# alt1.net
KiCad netlist of a schematic drawn in EAGLE
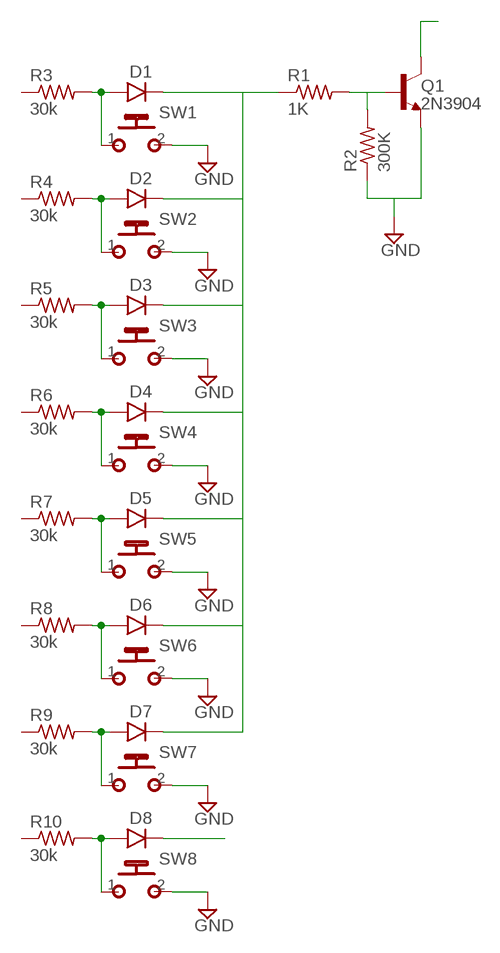
[diagram p0: schematic, sheet 1]

(export (version "E")
  (design (tool "Eeschema 10.0.6"))
  (components
    (comp (ref "D1")
      (value "1N4148-3")
      (footprint "eagle-import:DO35-3")
      (libsource (lib "eagle-import") (part "1N4148-3"))
    )
    (comp (ref "D2")
      (value "1N4148-3")
      (footprint "eagle-import:DO35-3")
      (libsource (lib "eagle-import") (part "1N4148-3"))
    )
    (comp (ref "D3")
      (value "1N4148-3")
      (footprint "eagle-import:DO35-3")
      (libsource (lib "eagle-import") (part "1N4148-3"))
    )
    (comp (ref "D4")
      (value "1N4148-3")
      (footprint "eagle-import:DO35-3")
      (libsource (lib "eagle-import") (part "1N4148-3"))
    )
    (comp (ref "D5")
      (value "1N4148-3")
      (footprint "eagle-import:DO35-3")
      (libsource (lib "eagle-import") (part "1N4148-3"))
    )
    (comp (ref "D6")
      (value "1N4148-3")
      (footprint "eagle-import:DO35-3")
      (libsource (lib "eagle-import") (part "1N4148-3"))
    )
    (comp (ref "D7")
      (value "1N4148-3")
      (footprint "eagle-import:DO35-3")
      (libsource (lib "eagle-import") (part "1N4148-3"))
    )
    (comp (ref "D8")
      (value "1N4148-3")
      (footprint "eagle-import:DO35-3")
      (libsource (lib "eagle-import") (part "1N4148-3"))
    )
    (comp (ref "Q1")
      (value "2N3904")
      (footprint "eagle-import:TO92-")
      (libsource (lib "eagle-import") (part "2N3904"))
    )
    (comp (ref "R1")
      (value "1K")
      (footprint "eagle-import:R0207_3")
      (libsource (lib "eagle-import") (part "6MM.3"))
    )
    (comp (ref "R2")
      (value "300K")
      (footprint "eagle-import:R0207_3")
      (libsource (lib "eagle-import") (part "6MM.3"))
    )
    (comp (ref "R3")
      (value "30k")
      (footprint "eagle-import:R0207_3")
      (libsource (lib "eagle-import") (part "6MM.3"))
    )
    (comp (ref "R4")
      (value "30k")
      (footprint "eagle-import:R0207_3")
      (libsource (lib "eagle-import") (part "6MM.3"))
    )
    (comp (ref "R5")
      (value "30k")
      (footprint "eagle-import:R0207_3")
      (libsource (lib "eagle-import") (part "6MM.3"))
    )
    (comp (ref "R6")
      (value "30k")
      (footprint "eagle-import:R0207_3")
      (libsource (lib "eagle-import") (part "6MM.3"))
    )
    (comp (ref "R7")
      (value "30k")
      (footprint "eagle-import:R0207_3")
      (libsource (lib "eagle-import") (part "6MM.3"))
    )
    (comp (ref "R8")
      (value "30k")
      (footprint "eagle-import:R0207_3")
      (libsource (lib "eagle-import") (part "6MM.3"))
    )
    (comp (ref "R9")
      (value "30k")
      (footprint "eagle-import:R0207_3")
      (libsource (lib "eagle-import") (part "6MM.3"))
    )
    (comp (ref "R10")
      (value "30k")
      (footprint "eagle-import:R0207_3")
      (libsource (lib "eagle-import") (part "6MM.3"))
    )
    (comp (ref "SW1")
      (value "MOMENTARYSPST1")
      (footprint "eagle-import:SPST")
      (libsource (lib "eagle-import") (part "MOMENTARYSPST1"))
    )
    (comp (ref "SW2")
      (value "MOMENTARYSPST1")
      (footprint "eagle-import:SPST")
      (libsource (lib "eagle-import") (part "MOMENTARYSPST1"))
    )
    (comp (ref "SW3")
      (value "MOMENTARYSPST1")
      (footprint "eagle-import:SPST")
      (libsource (lib "eagle-import") (part "MOMENTARYSPST1"))
    )
    (comp (ref "SW4")
      (value "MOMENTARYSPST1")
      (footprint "eagle-import:SPST")
      (libsource (lib "eagle-import") (part "MOMENTARYSPST1"))
    )
    (comp (ref "SW5")
      (value "MOMENTARYSPST1")
      (footprint "eagle-import:SPST")
      (libsource (lib "eagle-import") (part "MOMENTARYSPST1"))
    )
    (comp (ref "SW6")
      (value "MOMENTARYSPST1")
      (footprint "eagle-import:SPST")
      (libsource (lib "eagle-import") (part "MOMENTARYSPST1"))
    )
    (comp (ref "SW7")
      (value "MOMENTARYSPST1")
      (footprint "eagle-import:SPST")
      (libsource (lib "eagle-import") (part "MOMENTARYSPST1"))
    )
    (comp (ref "SW8")
      (value "MOMENTARYSPST1")
      (footprint "eagle-import:SPST")
      (libsource (lib "eagle-import") (part "MOMENTARYSPST1"))
    )
  )
  (nets
    (net (code "1") (name "GND") (class "Default")
      (node (ref "Q1") (pin "3") (pinfunction "E_3") (pintype "passive"))
      (node (ref "R2") (pin "1") (pinfunction "1_1") (pintype "passive"))
      (node (ref "SW1") (pin "2") (pinfunction "S_2") (pintype "passive"))
      (node (ref "SW2") (pin "2") (pinfunction "S_2") (pintype "passive"))
      (node (ref "SW3") (pin "2") (pinfunction "S_2") (pintype "passive"))
      (node (ref "SW4") (pin "2") (pinfunction "S_2") (pintype "passive"))
      (node (ref "SW5") (pin "2") (pinfunction "S_2") (pintype "passive"))
      (node (ref "SW6") (pin "2") (pinfunction "S_2") (pintype "passive"))
      (node (ref "SW7") (pin "2") (pinfunction "S_2") (pintype "passive"))
      (node (ref "SW8") (pin "2") (pinfunction "S_2") (pintype "passive"))
    )
    (net (code "2") (name "Net-(D1-PadC)") (class "Default")
      (node (ref "D1") (pin "C") (pinfunction "C_C") (pintype "passive"))
      (node (ref "D2") (pin "C") (pinfunction "C_C") (pintype "passive"))
      (node (ref "D3") (pin "C") (pinfunction "C_C") (pintype "passive"))
      (node (ref "D4") (pin "C") (pinfunction "C_C") (pintype "passive"))
      (node (ref "D5") (pin "C") (pinfunction "C_C") (pintype "passive"))
      (node (ref "D6") (pin "C") (pinfunction "C_C") (pintype "passive"))
      (node (ref "D7") (pin "C") (pinfunction "C_C") (pintype "passive"))
      (node (ref "R1") (pin "1") (pinfunction "1_1") (pintype "passive"))
    )
    (net (code "3") (name "Net-(Q1-B)") (class "Default")
      (node (ref "Q1") (pin "2") (pinfunction "B_2") (pintype "passive"))
      (node (ref "R1") (pin "2") (pinfunction "2_2") (pintype "passive"))
      (node (ref "R2") (pin "2") (pinfunction "2_2") (pintype "passive"))
    )
    (net (code "4") (name "Net-(SW1-P)") (class "Default")
      (node (ref "D1") (pin "A") (pinfunction "A_A") (pintype "passive"))
      (node (ref "R3") (pin "2") (pinfunction "2_2") (pintype "passive"))
      (node (ref "SW1") (pin "1") (pinfunction "P_1") (pintype "passive"))
    )
    (net (code "5") (name "Net-(SW2-P)") (class "Default")
      (node (ref "D2") (pin "A") (pinfunction "A_A") (pintype "passive"))
      (node (ref "R4") (pin "2") (pinfunction "2_2") (pintype "passive"))
      (node (ref "SW2") (pin "1") (pinfunction "P_1") (pintype "passive"))
    )
    (net (code "6") (name "Net-(SW3-P)") (class "Default")
      (node (ref "D3") (pin "A") (pinfunction "A_A") (pintype "passive"))
      (node (ref "R5") (pin "2") (pinfunction "2_2") (pintype "passive"))
      (node (ref "SW3") (pin "1") (pinfunction "P_1") (pintype "passive"))
    )
    (net (code "7") (name "Net-(SW4-P)") (class "Default")
      (node (ref "D4") (pin "A") (pinfunction "A_A") (pintype "passive"))
      (node (ref "R6") (pin "2") (pinfunction "2_2") (pintype "passive"))
      (node (ref "SW4") (pin "1") (pinfunction "P_1") (pintype "passive"))
    )
    (net (code "8") (name "Net-(SW5-P)") (class "Default")
      (node (ref "D5") (pin "A") (pinfunction "A_A") (pintype "passive"))
      (node (ref "R7") (pin "2") (pinfunction "2_2") (pintype "passive"))
      (node (ref "SW5") (pin "1") (pinfunction "P_1") (pintype "passive"))
    )
    (net (code "9") (name "Net-(SW6-P)") (class "Default")
      (node (ref "D6") (pin "A") (pinfunction "A_A") (pintype "passive"))
      (node (ref "R8") (pin "2") (pinfunction "2_2") (pintype "passive"))
      (node (ref "SW6") (pin "1") (pinfunction "P_1") (pintype "passive"))
    )
    (net (code "10") (name "Net-(SW7-P)") (class "Default")
      (node (ref "D7") (pin "A") (pinfunction "A_A") (pintype "passive"))
      (node (ref "R9") (pin "2") (pinfunction "2_2") (pintype "passive"))
      (node (ref "SW7") (pin "1") (pinfunction "P_1") (pintype "passive"))
    )
    (net (code "11") (name "Net-(SW8-P)") (class "Default")
      (node (ref "D8") (pin "A") (pinfunction "A_A") (pintype "passive"))
      (node (ref "R10") (pin "2") (pinfunction "2_2") (pintype "passive"))
      (node (ref "SW8") (pin "1") (pinfunction "P_1") (pintype "passive"))
    )
    (net (code "12") (name "unconnected-(D8-PadC)") (class "Default")
      (node (ref "D8") (pin "C") (pinfunction "C_C") (pintype "passive"))
    )
    (net (code "13") (name "unconnected-(Q1-C-Pad1)") (class "Default")
      (node (ref "Q1") (pin "1") (pinfunction "C_1") (pintype "passive"))
    )
    (net (code "14") (name "unconnected-(R3-Pad1)") (class "Default")
      (node (ref "R3") (pin "1") (pinfunction "1_1") (pintype "passive"))
    )
    (net (code "15") (name "unconnected-(R4-Pad1)") (class "Default")
      (node (ref "R4") (pin "1") (pinfunction "1_1") (pintype "passive"))
    )
    (net (code "16") (name "unconnected-(R5-Pad1)") (class "Default")
      (node (ref "R5") (pin "1") (pinfunction "1_1") (pintype "passive"))
    )
    (net (code "17") (name "unconnected-(R6-Pad1)") (class "Default")
      (node (ref "R6") (pin "1") (pinfunction "1_1") (pintype "passive"))
    )
    (net (code "18") (name "unconnected-(R7-Pad1)") (class "Default")
      (node (ref "R7") (pin "1") (pinfunction "1_1") (pintype "passive"))
    )
    (net (code "19") (name "unconnected-(R8-Pad1)") (class "Default")
      (node (ref "R8") (pin "1") (pinfunction "1_1") (pintype "passive"))
    )
    (net (code "20") (name "unconnected-(R9-Pad1)") (class "Default")
      (node (ref "R9") (pin "1") (pinfunction "1_1") (pintype "passive"))
    )
    (net (code "21") (name "unconnected-(R10-Pad1)") (class "Default")
      (node (ref "R10") (pin "1") (pinfunction "1_1") (pintype "passive"))
    )
  )
)
